# 06_LEDs.net
KiCad netlist of a schematic drawn in Altium Designer
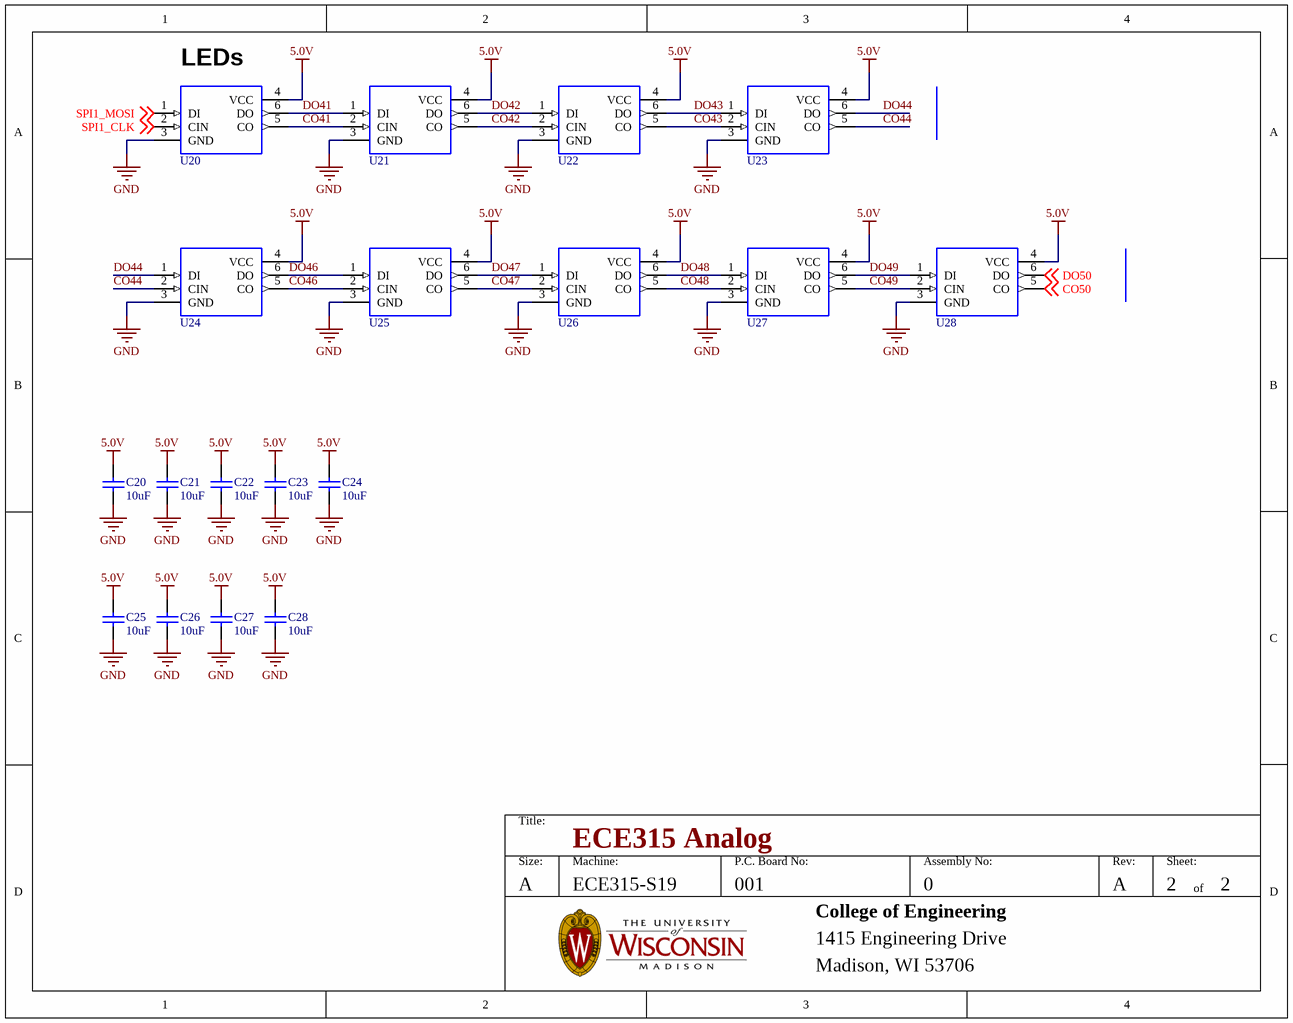
[diagram p0: 06_LEDs.SchDoc]

(export (version "E")
  (design (tool "Eeschema 10.0.6"))
  (components
    (comp (ref "C20")
      (value "10uF")
      (footprint "CAP_0805")
      (description "CAP CER 10UF 16V X7R 0805")
      (fields
        (field (name "MANUFACTURER") "Samsung")
        (field (name "MANUFACTURER PART NUMBER") "CL21A106KPCLQNC")
        (field (name "CAPACITANCE") "10uF")
      )
      (libsource (lib "ece315-2018-fall") (part "CAP_0805_U_010.00"))
    )
    (comp (ref "C21")
      (value "10uF")
      (footprint "CAP_0805")
      (description "CAP CER 10UF 16V X7R 0805")
      (fields
        (field (name "MANUFACTURER") "Samsung")
        (field (name "MANUFACTURER PART NUMBER") "CL21A106KPCLQNC")
        (field (name "CAPACITANCE") "10uF")
      )
      (libsource (lib "ece315-2018-fall") (part "CAP_0805_U_010.00"))
    )
    (comp (ref "C22")
      (value "10uF")
      (footprint "CAP_0805")
      (description "CAP CER 10UF 16V X7R 0805")
      (fields
        (field (name "MANUFACTURER") "Samsung")
        (field (name "MANUFACTURER PART NUMBER") "CL21A106KPCLQNC")
        (field (name "CAPACITANCE") "10uF")
      )
      (libsource (lib "ece315-2018-fall") (part "CAP_0805_U_010.00"))
    )
    (comp (ref "C23")
      (value "10uF")
      (footprint "CAP_0805")
      (description "CAP CER 10UF 16V X7R 0805")
      (fields
        (field (name "MANUFACTURER") "Samsung")
        (field (name "MANUFACTURER PART NUMBER") "CL21A106KPCLQNC")
        (field (name "CAPACITANCE") "10uF")
      )
      (libsource (lib "ece315-2018-fall") (part "CAP_0805_U_010.00"))
    )
    (comp (ref "C24")
      (value "10uF")
      (footprint "CAP_0805")
      (description "CAP CER 10UF 16V X7R 0805")
      (fields
        (field (name "MANUFACTURER") "Samsung")
        (field (name "MANUFACTURER PART NUMBER") "CL21A106KPCLQNC")
        (field (name "CAPACITANCE") "10uF")
      )
      (libsource (lib "ece315-2018-fall") (part "CAP_0805_U_010.00"))
    )
    (comp (ref "C25")
      (value "10uF")
      (footprint "CAP_0805")
      (description "CAP CER 10UF 16V X7R 0805")
      (fields
        (field (name "MANUFACTURER") "Samsung")
        (field (name "MANUFACTURER PART NUMBER") "CL21A106KPCLQNC")
        (field (name "CAPACITANCE") "10uF")
      )
      (libsource (lib "ece315-2018-fall") (part "CAP_0805_U_010.00"))
    )
    (comp (ref "C26")
      (value "10uF")
      (footprint "CAP_0805")
      (description "CAP CER 10UF 16V X7R 0805")
      (fields
        (field (name "MANUFACTURER") "Samsung")
        (field (name "MANUFACTURER PART NUMBER") "CL21A106KPCLQNC")
        (field (name "CAPACITANCE") "10uF")
      )
      (libsource (lib "ece315-2018-fall") (part "CAP_0805_U_010.00"))
    )
    (comp (ref "C27")
      (value "10uF")
      (footprint "CAP_0805")
      (description "CAP CER 10UF 16V X7R 0805")
      (fields
        (field (name "MANUFACTURER") "Samsung")
        (field (name "MANUFACTURER PART NUMBER") "CL21A106KPCLQNC")
        (field (name "CAPACITANCE") "10uF")
      )
      (libsource (lib "ece315-2018-fall") (part "CAP_0805_U_010.00"))
    )
    (comp (ref "C28")
      (value "10uF")
      (footprint "CAP_0805")
      (description "CAP CER 10UF 16V X7R 0805")
      (fields
        (field (name "MANUFACTURER") "Samsung")
        (field (name "MANUFACTURER PART NUMBER") "CL21A106KPCLQNC")
        (field (name "CAPACITANCE") "10uF")
      )
      (libsource (lib "ece315-2018-fall") (part "CAP_0805_U_010.00"))
    )
    (comp (ref "U20")
      (value "IC_APA102C")
      (footprint "APA102C")
      (description "APA102C LED")
      (libsource (lib "ece315-2018-fall") (part "IC_APA102C"))
    )
    (comp (ref "U21")
      (value "IC_APA102C")
      (footprint "APA102C")
      (description "APA102C LED")
      (libsource (lib "ece315-2018-fall") (part "IC_APA102C"))
    )
    (comp (ref "U22")
      (value "IC_APA102C")
      (footprint "APA102C")
      (description "APA102C LED")
      (libsource (lib "ece315-2018-fall") (part "IC_APA102C"))
    )
    (comp (ref "U23")
      (value "IC_APA102C")
      (footprint "APA102C")
      (description "APA102C LED")
      (libsource (lib "ece315-2018-fall") (part "IC_APA102C"))
    )
    (comp (ref "U24")
      (value "IC_APA102C")
      (footprint "APA102C")
      (description "APA102C LED")
      (libsource (lib "ece315-2018-fall") (part "IC_APA102C"))
    )
    (comp (ref "U25")
      (value "IC_APA102C")
      (footprint "APA102C")
      (description "APA102C LED")
      (libsource (lib "ece315-2018-fall") (part "IC_APA102C"))
    )
    (comp (ref "U26")
      (value "IC_APA102C")
      (footprint "APA102C")
      (description "APA102C LED")
      (libsource (lib "ece315-2018-fall") (part "IC_APA102C"))
    )
    (comp (ref "U27")
      (value "IC_APA102C")
      (footprint "APA102C")
      (description "APA102C LED")
      (libsource (lib "ece315-2018-fall") (part "IC_APA102C"))
    )
    (comp (ref "U28")
      (value "IC_APA102C")
      (footprint "APA102C")
      (description "APA102C LED")
      (libsource (lib "ece315-2018-fall") (part "IC_APA102C"))
    )
  )
  (nets
    (net (code "1") (name "/CO41") (class "Default")
      (node (ref "U20") (pin "5") (pinfunction "CO_5") (pintype "output"))
      (node (ref "U21") (pin "2") (pinfunction "CIN_2") (pintype "input"))
    )
    (net (code "2") (name "/CO42") (class "Default")
      (node (ref "U21") (pin "5") (pinfunction "CO_5") (pintype "output"))
      (node (ref "U22") (pin "2") (pinfunction "CIN_2") (pintype "input"))
    )
    (net (code "3") (name "/CO43") (class "Default")
      (node (ref "U22") (pin "5") (pinfunction "CO_5") (pintype "output"))
      (node (ref "U23") (pin "2") (pinfunction "CIN_2") (pintype "input"))
    )
    (net (code "4") (name "/CO44") (class "Default")
      (node (ref "U23") (pin "5") (pinfunction "CO_5") (pintype "output"))
      (node (ref "U24") (pin "2") (pinfunction "CIN_2") (pintype "input"))
    )
    (net (code "5") (name "/CO46") (class "Default")
      (node (ref "U24") (pin "5") (pinfunction "CO_5") (pintype "output"))
      (node (ref "U25") (pin "2") (pinfunction "CIN_2") (pintype "input"))
    )
    (net (code "6") (name "/CO47") (class "Default")
      (node (ref "U25") (pin "5") (pinfunction "CO_5") (pintype "output"))
      (node (ref "U26") (pin "2") (pinfunction "CIN_2") (pintype "input"))
    )
    (net (code "7") (name "/CO48") (class "Default")
      (node (ref "U26") (pin "5") (pinfunction "CO_5") (pintype "output"))
      (node (ref "U27") (pin "2") (pinfunction "CIN_2") (pintype "input"))
    )
    (net (code "8") (name "/CO49") (class "Default")
      (node (ref "U27") (pin "5") (pinfunction "CO_5") (pintype "output"))
      (node (ref "U28") (pin "2") (pinfunction "CIN_2") (pintype "input"))
    )
    (net (code "9") (name "/DO41") (class "Default")
      (node (ref "U20") (pin "6") (pinfunction "DO_6") (pintype "output"))
      (node (ref "U21") (pin "1") (pinfunction "DI_1") (pintype "input"))
    )
    (net (code "10") (name "/DO42") (class "Default")
      (node (ref "U21") (pin "6") (pinfunction "DO_6") (pintype "output"))
      (node (ref "U22") (pin "1") (pinfunction "DI_1") (pintype "input"))
    )
    (net (code "11") (name "/DO43") (class "Default")
      (node (ref "U22") (pin "6") (pinfunction "DO_6") (pintype "output"))
      (node (ref "U23") (pin "1") (pinfunction "DI_1") (pintype "input"))
    )
    (net (code "12") (name "/DO44") (class "Default")
      (node (ref "U23") (pin "6") (pinfunction "DO_6") (pintype "output"))
      (node (ref "U24") (pin "1") (pinfunction "DI_1") (pintype "input"))
    )
    (net (code "13") (name "/DO46") (class "Default")
      (node (ref "U24") (pin "6") (pinfunction "DO_6") (pintype "output"))
      (node (ref "U25") (pin "1") (pinfunction "DI_1") (pintype "input"))
    )
    (net (code "14") (name "/DO47") (class "Default")
      (node (ref "U25") (pin "6") (pinfunction "DO_6") (pintype "output"))
      (node (ref "U26") (pin "1") (pinfunction "DI_1") (pintype "input"))
    )
    (net (code "15") (name "/DO48") (class "Default")
      (node (ref "U26") (pin "6") (pinfunction "DO_6") (pintype "output"))
      (node (ref "U27") (pin "1") (pinfunction "DI_1") (pintype "input"))
    )
    (net (code "16") (name "/DO49") (class "Default")
      (node (ref "U27") (pin "6") (pinfunction "DO_6") (pintype "output"))
      (node (ref "U28") (pin "1") (pinfunction "DI_1") (pintype "input"))
    )
    (net (code "17") (name "5.0V") (class "Default")
      (node (ref "C20") (pin "2") (pinfunction "2_2") (pintype "passive"))
      (node (ref "C21") (pin "2") (pinfunction "2_2") (pintype "passive"))
      (node (ref "C22") (pin "2") (pinfunction "2_2") (pintype "passive"))
      (node (ref "C23") (pin "2") (pinfunction "2_2") (pintype "passive"))
      (node (ref "C24") (pin "2") (pinfunction "2_2") (pintype "passive"))
      (node (ref "C25") (pin "2") (pinfunction "2_2") (pintype "passive"))
      (node (ref "C26") (pin "2") (pinfunction "2_2") (pintype "passive"))
      (node (ref "C27") (pin "2") (pinfunction "2_2") (pintype "passive"))
      (node (ref "C28") (pin "2") (pinfunction "2_2") (pintype "passive"))
      (node (ref "U20") (pin "4") (pinfunction "VCC_4") (pintype "power_in"))
      (node (ref "U21") (pin "4") (pinfunction "VCC_4") (pintype "power_in"))
      (node (ref "U22") (pin "4") (pinfunction "VCC_4") (pintype "power_in"))
      (node (ref "U23") (pin "4") (pinfunction "VCC_4") (pintype "power_in"))
      (node (ref "U24") (pin "4") (pinfunction "VCC_4") (pintype "power_in"))
      (node (ref "U25") (pin "4") (pinfunction "VCC_4") (pintype "power_in"))
      (node (ref "U26") (pin "4") (pinfunction "VCC_4") (pintype "power_in"))
      (node (ref "U27") (pin "4") (pinfunction "VCC_4") (pintype "power_in"))
      (node (ref "U28") (pin "4") (pinfunction "VCC_4") (pintype "power_in"))
    )
    (net (code "18") (name "CO50") (class "Default")
      (node (ref "U28") (pin "5") (pinfunction "CO_5") (pintype "output"))
    )
    (net (code "19") (name "DO50") (class "Default")
      (node (ref "U28") (pin "6") (pinfunction "DO_6") (pintype "output"))
    )
    (net (code "20") (name "GND") (class "Default")
      (node (ref "C20") (pin "1") (pinfunction "1_1") (pintype "passive"))
      (node (ref "C21") (pin "1") (pinfunction "1_1") (pintype "passive"))
      (node (ref "C22") (pin "1") (pinfunction "1_1") (pintype "passive"))
      (node (ref "C23") (pin "1") (pinfunction "1_1") (pintype "passive"))
      (node (ref "C24") (pin "1") (pinfunction "1_1") (pintype "passive"))
      (node (ref "C25") (pin "1") (pinfunction "1_1") (pintype "passive"))
      (node (ref "C26") (pin "1") (pinfunction "1_1") (pintype "passive"))
      (node (ref "C27") (pin "1") (pinfunction "1_1") (pintype "passive"))
      (node (ref "C28") (pin "1") (pinfunction "1_1") (pintype "passive"))
      (node (ref "U20") (pin "3") (pinfunction "GND_3") (pintype "power_in"))
      (node (ref "U21") (pin "3") (pinfunction "GND_3") (pintype "power_in"))
      (node (ref "U22") (pin "3") (pinfunction "GND_3") (pintype "power_in"))
      (node (ref "U23") (pin "3") (pinfunction "GND_3") (pintype "power_in"))
      (node (ref "U24") (pin "3") (pinfunction "GND_3") (pintype "power_in"))
      (node (ref "U25") (pin "3") (pinfunction "GND_3") (pintype "power_in"))
      (node (ref "U26") (pin "3") (pinfunction "GND_3") (pintype "power_in"))
      (node (ref "U27") (pin "3") (pinfunction "GND_3") (pintype "power_in"))
      (node (ref "U28") (pin "3") (pinfunction "GND_3") (pintype "power_in"))
    )
    (net (code "21") (name "SPI1_CLK") (class "Default")
      (node (ref "U20") (pin "2") (pinfunction "CIN_2") (pintype "input"))
    )
    (net (code "22") (name "SPI1_MOSI") (class "Default")
      (node (ref "U20") (pin "1") (pinfunction "DI_1") (pintype "input"))
    )
  )
)
